# Control_and_Sample.net
KiCad netlist of a schematic drawn in Altium Designer
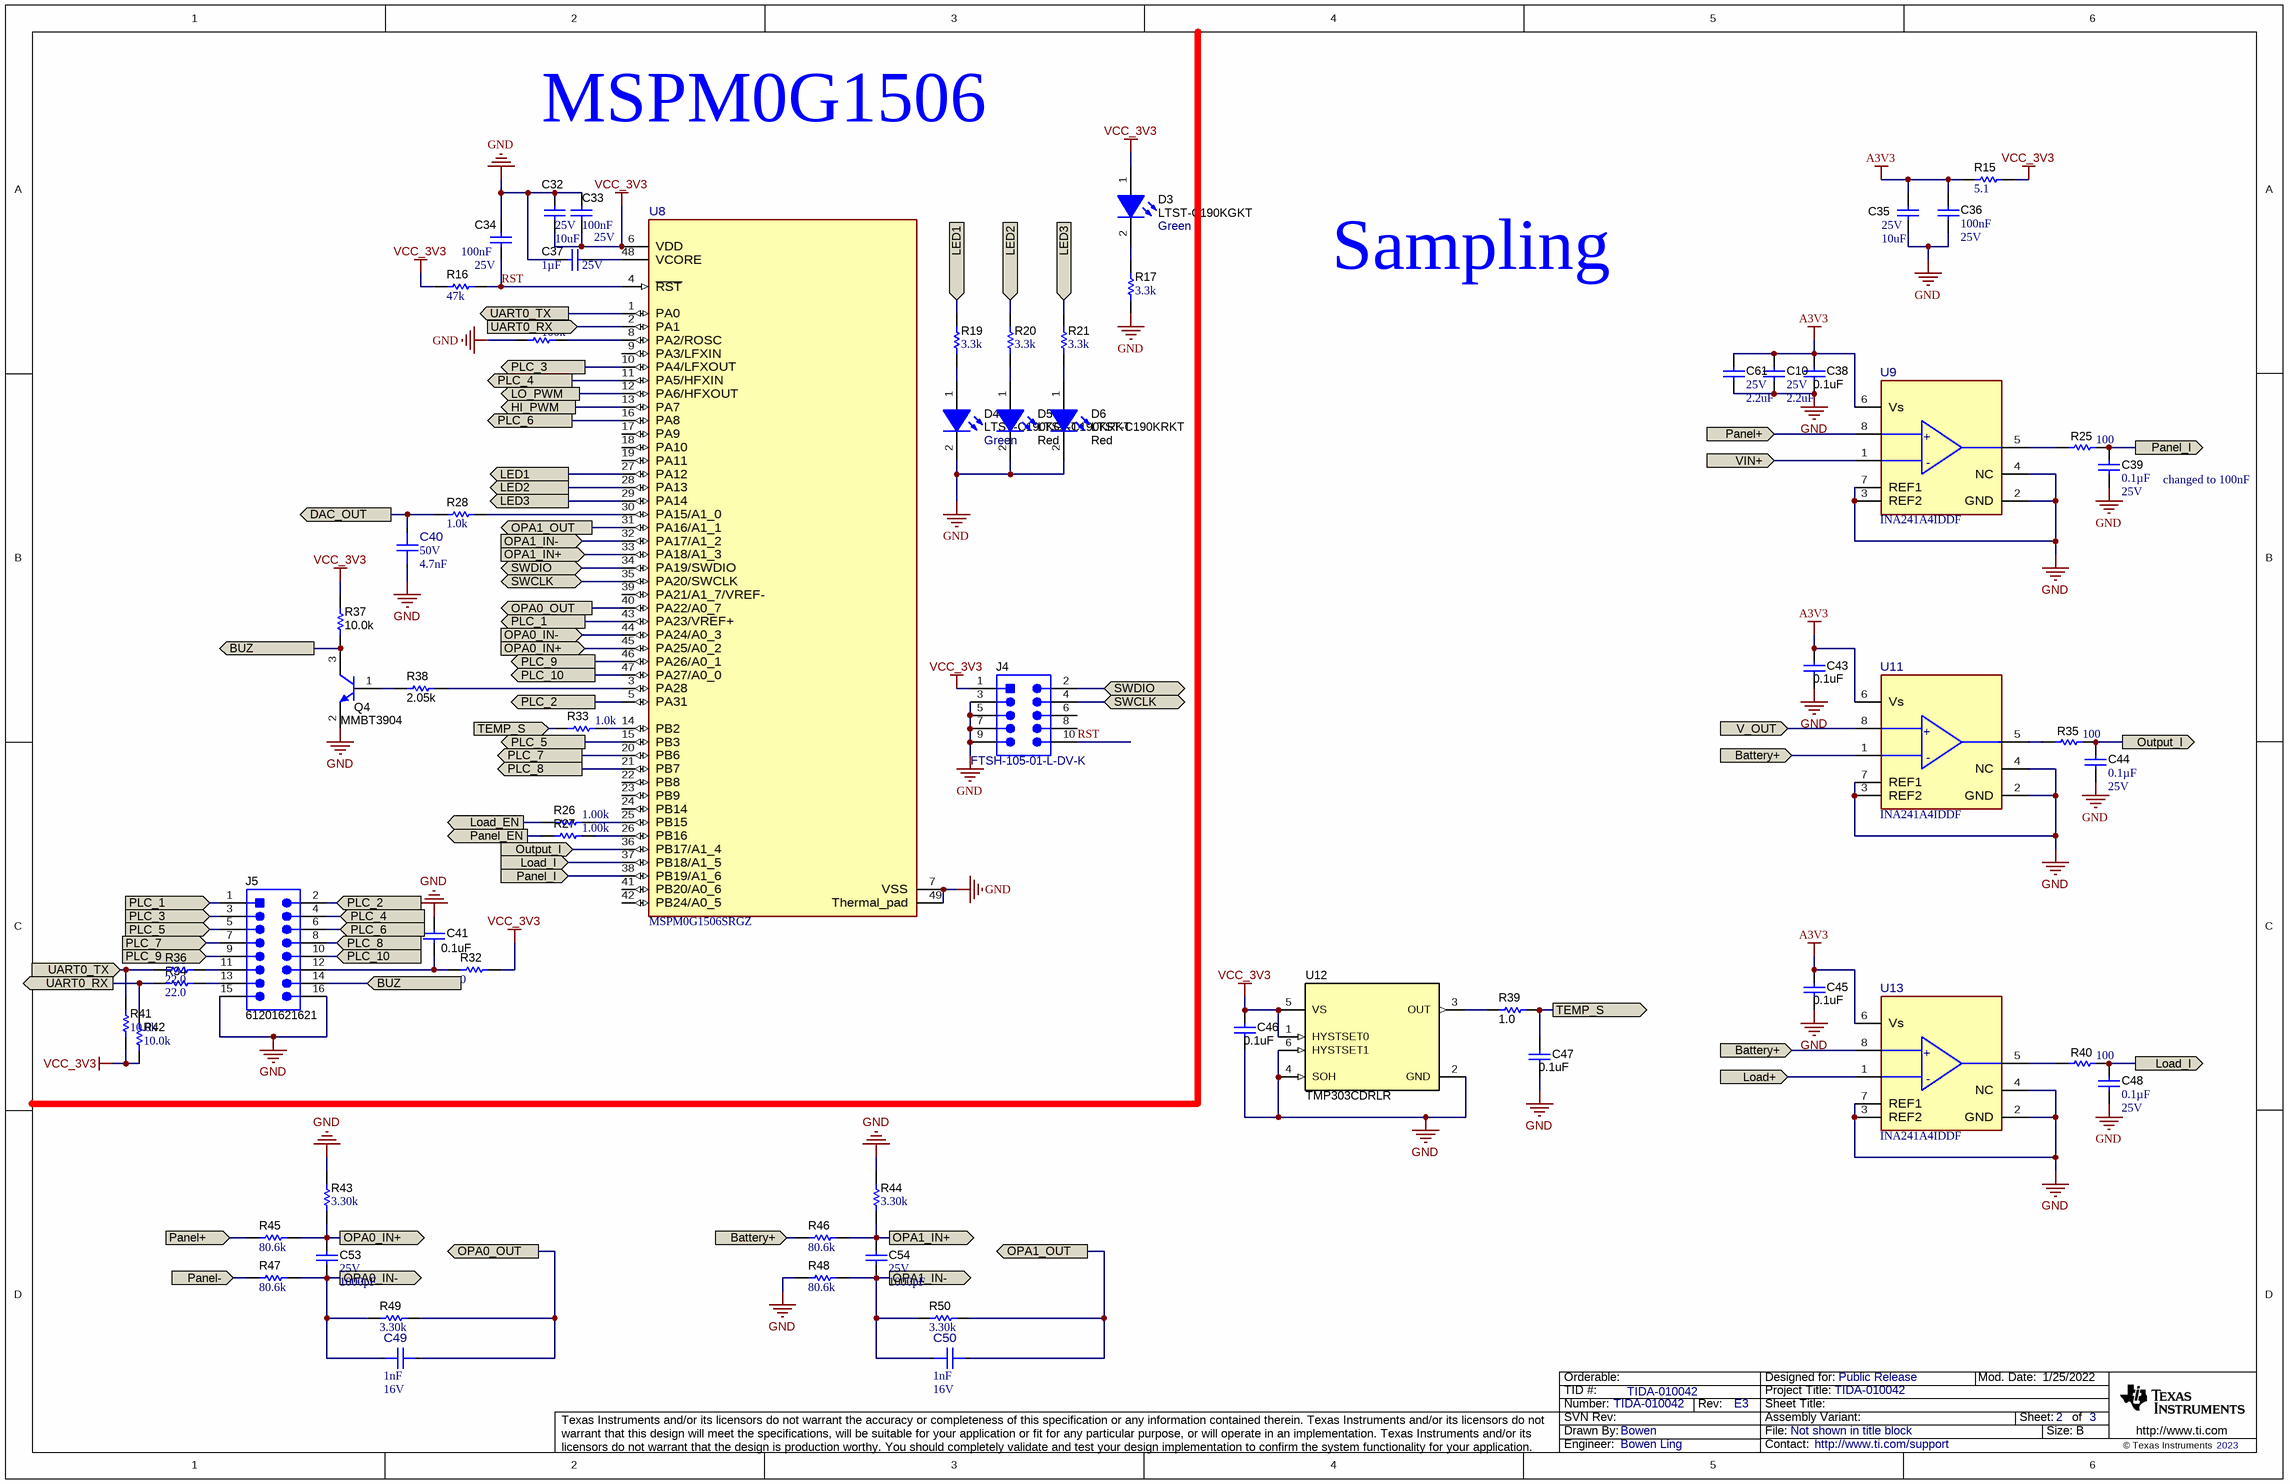
[diagram p0: Control and Sample.SchDoc]

(export (version "E")
  (design (tool "Eeschema 10.0.6"))
  (components
    (comp (ref "C10")
      (value "C1005X5R1E225K050BC")
      (footprint "0402")
      (description "CAP, CERM, 2.2 uF, 25 V, +/- 10%, X5R, 0402")
      (fields
        (field (name "MANUFACTURER") "TDK")
        (field (name "VDC_V") "25V")
        (field (name "VALUEDISPLAYED") "2.2uF")
        (field (name "PUBLISHER") "Texas Instruments")
      )
      (libsource (lib "Altium Vault - TI") (part "Capacitor"))
    )
    (comp (ref "C32")
      (value "GRM31CR71E106KA12L")
      (footprint "1206_180")
      (description "CAP, CERM, 10 uF, 25 V, +/- 10%, X7R, 1206")
      (fields
        (field (name "MANUFACTURER") "MuRata")
        (field (name "VDC_V") "25V")
        (field (name "VALUEDISPLAYED") "10uF")
        (field (name "PUBLISHER") "Texas Instruments")
      )
      (libsource (lib "Altium Vault - TI") (part "Capacitor"))
    )
    (comp (ref "C33")
      (value "GRM188R71E104KA01D")
      (footprint "0603")
      (description "CAP, CERM, 0.1 uF, 25 V, +/- 10%, X7R, 0603")
      (fields
        (field (name "MANUFACTURER") "MuRata")
        (field (name "CAP_F") "100nF")
        (field (name "VDC_V") "25V")
        (field (name "PUBLISHER") "Texas Instruments")
      )
      (libsource (lib "Altium Vault - TI") (part "Capacitor"))
    )
    (comp (ref "C34")
      (value "GRM188R71E104KA01D")
      (footprint "0603")
      (description "CAP, CERM, 0.1 uF, 25 V, +/- 10%, X7R, 0603")
      (fields
        (field (name "MANUFACTURER") "MuRata")
        (field (name "CAP_F") "100nF")
        (field (name "VDC_V") "25V")
        (field (name "PUBLISHER") "Texas Instruments")
      )
      (libsource (lib "Altium Vault - TI") (part "Capacitor"))
    )
    (comp (ref "C35")
      (value "GRM31CR71E106KA12L")
      (footprint "1206_180")
      (description "CAP, CERM, 10 uF, 25 V, +/- 10%, X7R, 1206")
      (fields
        (field (name "MANUFACTURER") "MuRata")
        (field (name "VDC_V") "25V")
        (field (name "VALUEDISPLAYED") "10uF")
        (field (name "PUBLISHER") "Texas Instruments")
      )
      (libsource (lib "Altium Vault - TI") (part "Capacitor"))
    )
    (comp (ref "C36")
      (value "GRM188R71E104KA01D")
      (footprint "0603")
      (description "CAP, CERM, 0.1 uF, 25 V, +/- 10%, X7R, 0603")
      (fields
        (field (name "MANUFACTURER") "MuRata")
        (field (name "CAP_F") "100nF")
        (field (name "VDC_V") "25V")
        (field (name "PUBLISHER") "Texas Instruments")
      )
      (libsource (lib "Altium Vault - TI") (part "Capacitor"))
    )
    (comp (ref "C37")
      (value "06033C105KAT2A")
      (footprint "0603")
      (description "CAP, CERM, 1 uF, 25 V, +/- 10%, X7R, 0603")
      (fields
        (field (name "MANUFACTURER") "AVX")
        (field (name "CAP_F") "1µF")
        (field (name "VDC_V") "25V")
        (field (name "PUBLISHER") "Texas Instruments")
      )
      (libsource (lib "Altium Vault - TI") (part "Capacitor"))
    )
    (comp (ref "C38")
      (value "GMK107BJ104KAHT")
      (footprint "0603")
      (description "CAP CER 0.1UF 25V X5R 0603")
      (fields
        (field (name "MANUFACTURER") "Taiyo Yuden")
        (field (name "PARTNUMBER") "TMK107BJ104KA-T")
        (field (name "VALUEDISPLAYED") "0.1uF")
        (field (name "PUBLISHER") "Texas Instruments")
      )
      (libsource (lib "Altium Vault - TI") (part "CMP-0007044-5"))
    )
    (comp (ref "C39")
      (value "GCM155L81E104KE02D")
      (footprint "0402")
      (description "CAP, CERM, 0.1 µF, 25 V,+/- 10%, X8L, AEC-Q200 Grade 0, 0402")
      (fields
        (field (name "MANUFACTURER") "MuRata")
        (field (name "VALUEDISPLAYED") "0.1µF")
        (field (name "VDC_V") "25V")
      )
      (libsource (lib "Altium Vault - TI") (part "Capacitor"))
    )
    (comp (ref "C40")
      (value "GRM188R71H472KA01J")
      (footprint "FP-GRM188R71H472KA01B_0603-MFG")
      (description "Multilayer Ceramic Capacitors MLCC - SMD/SMT 0603 4700pF 50volt X7R +/-10%")
      (fields
        (field (name "MOUSER PART NUMBER") "81-GRM18R71H472KA01B")
        (field (name "VDC_V") "50V")
        (field (name "CAP_F") "4.7nF")
        (field (name "PART NUMBER") "GRM188R71H472KA01B")
      )
      (libsource (lib "Altium Vault - TI") (part "SYM-GRM188R71H472KA01B"))
    )
    (comp (ref "C41")
      (value "GMK107BJ104KAHT")
      (footprint "0603")
      (description "CAP CER 0.1UF 25V X5R 0603")
      (fields
        (field (name "MANUFACTURER") "Taiyo Yuden")
        (field (name "PARTNUMBER") "TMK107BJ104KA-T")
        (field (name "VALUEDISPLAYED") "0.1uF")
        (field (name "PUBLISHER") "Texas Instruments")
      )
      (libsource (lib "Altium Vault - TI") (part "CMP-0007044-5"))
    )
    (comp (ref "C43")
      (value "GMK107BJ104KAHT")
      (footprint "0603")
      (description "CAP CER 0.1UF 25V X5R 0603")
      (fields
        (field (name "MANUFACTURER") "Taiyo Yuden")
        (field (name "PARTNUMBER") "TMK107BJ104KA-T")
        (field (name "VALUEDISPLAYED") "0.1uF")
        (field (name "PUBLISHER") "Texas Instruments")
      )
      (libsource (lib "Altium Vault - TI") (part "CMP-0007044-5"))
    )
    (comp (ref "C44")
      (value "GCM155L81E104KE02D")
      (footprint "0402")
      (description "CAP, CERM, 0.1 µF, 25 V,+/- 10%, X8L, AEC-Q200 Grade 0, 0402")
      (fields
        (field (name "MANUFACTURER") "MuRata")
        (field (name "VALUEDISPLAYED") "0.1µF")
        (field (name "VDC_V") "25V")
      )
      (libsource (lib "Altium Vault - TI") (part "Capacitor"))
    )
    (comp (ref "C45")
      (value "GMK107BJ104KAHT")
      (footprint "0603")
      (description "CAP CER 0.1UF 25V X5R 0603")
      (fields
        (field (name "MANUFACTURER") "Taiyo Yuden")
        (field (name "PARTNUMBER") "TMK107BJ104KA-T")
        (field (name "VALUEDISPLAYED") "0.1uF")
        (field (name "PUBLISHER") "Texas Instruments")
      )
      (libsource (lib "Altium Vault - TI") (part "CMP-0007044-5"))
    )
    (comp (ref "C46")
      (value "GMK107BJ104KAHT")
      (footprint "0603")
      (description "CAP CER 0.1UF 25V X5R 0603")
      (fields
        (field (name "MANUFACTURER") "Taiyo Yuden")
        (field (name "PARTNUMBER") "TMK107BJ104KA-T")
        (field (name "VALUEDISPLAYED") "0.1uF")
        (field (name "PUBLISHER") "Texas Instruments")
      )
      (libsource (lib "Altium Vault - TI") (part "CMP-0007044-5"))
    )
    (comp (ref "C47")
      (value "GMK107BJ104KAHT")
      (footprint "0603")
      (description "CAP CER 0.1UF 25V X5R 0603")
      (fields
        (field (name "MANUFACTURER") "Taiyo Yuden")
        (field (name "PARTNUMBER") "TMK107BJ104KA-T")
        (field (name "VALUEDISPLAYED") "0.1uF")
        (field (name "PUBLISHER") "Texas Instruments")
      )
      (libsource (lib "Altium Vault - TI") (part "CMP-0007044-5"))
    )
    (comp (ref "C48")
      (value "GCM155L81E104KE02D")
      (footprint "0402")
      (description "CAP, CERM, 0.1 µF, 25 V,+/- 10%, X8L, AEC-Q200 Grade 0, 0402")
      (fields
        (field (name "MANUFACTURER") "MuRata")
        (field (name "VALUEDISPLAYED") "0.1µF")
        (field (name "VDC_V") "25V")
      )
      (libsource (lib "Altium Vault - TI") (part "Capacitor"))
    )
    (comp (ref "C49")
      (value "CC0603KRX7R7BB102")
      (footprint "FP-CC0603KRX7R7BB102_0603-MFG")
      (description "1000 pF ±10% 16V Ceramic Capacitor X7R 0603 (1608 Metric)")
      (fields
        (field (name "MOUSER PART NUMBER") "603-CC603KRX7R7BB102")
        (field (name "MANUFACTURER") "YAGEO")
        (field (name "CAP_F") "1nF")
        (field (name "VDC_V") "16V")
      )
      (libsource (lib "Altium Vault - TI") (part "SYM-CC0603KRX7R7BB102"))
    )
    (comp (ref "C50")
      (value "CC0603KRX7R7BB102")
      (footprint "FP-CC0603KRX7R7BB102_0603-MFG")
      (description "1000 pF ±10% 16V Ceramic Capacitor X7R 0603 (1608 Metric)")
      (fields
        (field (name "MOUSER PART NUMBER") "603-CC603KRX7R7BB102")
        (field (name "MANUFACTURER") "YAGEO")
        (field (name "CAP_F") "1nF")
        (field (name "VDC_V") "16V")
      )
      (libsource (lib "Altium Vault - TI") (part "SYM-CC0603KRX7R7BB102"))
    )
    (comp (ref "C53")
      (value "C0402C102J3RACTU")
      (footprint "0402")
      (description "CAP, CERM, 1000 pF, 25 V, +/- 5%, X7R, 0402")
      (fields
        (field (name "MANUFACTURER") "Kemet")
        (field (name "VDC_V") "25V")
        (field (name "VALUEDISPLAYED") "1000pF")
        (field (name "PUBLISHER") "Texas Instruments")
      )
      (libsource (lib "Altium Vault - TI") (part "Capacitor"))
    )
    (comp (ref "C54")
      (value "C0402C102J3RACTU")
      (footprint "0402")
      (description "CAP, CERM, 1000 pF, 25 V, +/- 5%, X7R, 0402")
      (fields
        (field (name "MANUFACTURER") "Kemet")
        (field (name "VDC_V") "25V")
        (field (name "VALUEDISPLAYED") "1000pF")
        (field (name "PUBLISHER") "Texas Instruments")
      )
      (libsource (lib "Altium Vault - TI") (part "Capacitor"))
    )
    (comp (ref "C61")
      (value "C1005X5R1E225K050BC")
      (footprint "0402")
      (description "CAP, CERM, 2.2 uF, 25 V, +/- 10%, X5R, 0402")
      (fields
        (field (name "MANUFACTURER") "TDK")
        (field (name "VDC_V") "25V")
        (field (name "VALUEDISPLAYED") "2.2uF")
        (field (name "PUBLISHER") "Texas Instruments")
      )
      (libsource (lib "Altium Vault - TI") (part "Capacitor"))
    )
    (comp (ref "D3")
      (value "LTST-C190KGKT")
      (footprint "LED_LTST-C190_G")
      (description "LED, Green, SMD")
      (fields (field (name "ALTIUM_VALUE") "Green") (field (name "MANUFACTURER") "Lite-On"))
      (libsource (lib "Altium Vault - TI") (part "LED"))
    )
    (comp (ref "D4")
      (value "LTST-C190KGKT")
      (footprint "LED_LTST-C190_G")
      (description "LED, Green, SMD")
      (fields (field (name "ALTIUM_VALUE") "Green") (field (name "MANUFACTURER") "Lite-On"))
      (libsource (lib "Altium Vault - TI") (part "LED"))
    )
    (comp (ref "D5")
      (value "LTST-C190KRKT")
      (footprint "LED_LTST-C190_Red")
      (description "LED, Red, SMD")
      (fields (field (name "ALTIUM_VALUE") "Red") (field (name "MANUFACTURER") "Lite-On"))
      (libsource (lib "Altium Vault - TI") (part "LED"))
    )
    (comp (ref "D6")
      (value "LTST-C190KRKT")
      (footprint "LED_LTST-C190_Red")
      (description "LED, Red, SMD")
      (fields (field (name "ALTIUM_VALUE") "Red") (field (name "MANUFACTURER") "Lite-On"))
      (libsource (lib "Altium Vault - TI") (part "LED"))
    )
    (comp (ref "J4")
      (value "FTSH-105-01-L-DV-K")
      (footprint "Samtec_FTSH-105-01-x-DV-K")
      (description "Header(Shrouded), 1.27mm, 5x2, Gold, SMT")
      (fields (field (name "MANUFACTURER") "Samtec") (field (name "PUBLISHER") "Texas Instruments"))
      (libsource (lib "Altium Vault - TI") (part "Header_5x2"))
    )
    (comp (ref "J5")
      (value "61201621621")
      (footprint "Wurth_61201621621")
      (description "Header(Shrouded), 2.54mm, 8x2, Gold, TH")
      (fields (field (name "MANUFACTURER") "Wurth Elektronik") (field (name "PUBLISHER") "Texas Instruments"))
      (libsource (lib "Altium Vault - TI") (part "Header_8x2"))
    )
    (comp (ref "Q4")
      (value "MMBT3904")
      (footprint "SOT-23")
      (description "TRANS NPN 40V 0.2A SOT23")
      (fields
        (field (name "PARTNUMBER") "MMBT3904-TP")
        (field (name "MANUFACTURER") "Micro Commercial Co")
        (field (name "PUBLISHER") "Texas Instruments")
      )
      (libsource (lib "Altium Vault - TI") (part "CMP-0000386-2"))
    )
    (comp (ref "R15")
      (value "CRCW06035R10JNEA")
      (footprint "0603")
      (description "RES, 5.1, 5%, 0.1 W, 0603")
      (fields
        (field (name "MANUFACTURER") "Vishay-Dale")
        (field (name "VALUEDISPLAYED") "5.1")
        (field (name "PUBLISHER") "Texas Instruments")
      )
      (libsource (lib "Altium Vault - TI") (part "Resistor"))
    )
    (comp (ref "R16")
      (value "RC0603JR-0747KL")
      (footprint "0603")
      (description "RES, 47 k, 5%, 0.1 W, 0603")
      (fields (field (name "MANUFACTURER") "Yageo") (field (name "VALUEDISPLAYED") "47k"))
      (libsource (lib "Altium Vault - TI") (part "Resistor"))
    )
    (comp (ref "R17")
      (value "CRCW06033K30JNEA")
      (footprint "0603")
      (description "RES, 3.3 k, 5%, 0.1 W, AEC-Q200 Grade 0, 0603")
      (fields (field (name "MANUFACTURER") "Vishay-Dale") (field (name "VALUEDISPLAYED") "3.3k"))
      (libsource (lib "Altium Vault - TI") (part "Resistor"))
    )
    (comp (ref "R18")
      (value "RT0603BRD07100KL")
      (footprint "0603")
      (description "RES, 100 k, 0.1%, 0.1 W, 0603")
      (fields
        (field (name "MANUFACTURER") "Yageo America")
        (field (name "VALUEDISPLAYED") "100k")
        (field (name "PUBLISHER") "Texas Instruments")
      )
      (libsource (lib "Altium Vault - TI") (part "Resistor"))
    )
    (comp (ref "R19")
      (value "CRCW06033K30JNEA")
      (footprint "0603")
      (description "RES, 3.3 k, 5%, 0.1 W, AEC-Q200 Grade 0, 0603")
      (fields (field (name "MANUFACTURER") "Vishay-Dale") (field (name "VALUEDISPLAYED") "3.3k"))
      (libsource (lib "Altium Vault - TI") (part "Resistor"))
    )
    (comp (ref "R20")
      (value "CRCW06033K30JNEA")
      (footprint "0603")
      (description "RES, 3.3 k, 5%, 0.1 W, AEC-Q200 Grade 0, 0603")
      (fields (field (name "MANUFACTURER") "Vishay-Dale") (field (name "VALUEDISPLAYED") "3.3k"))
      (libsource (lib "Altium Vault - TI") (part "Resistor"))
    )
    (comp (ref "R21")
      (value "CRCW06033K30JNEA")
      (footprint "0603")
      (description "RES, 3.3 k, 5%, 0.1 W, AEC-Q200 Grade 0, 0603")
      (fields (field (name "MANUFACTURER") "Vishay-Dale") (field (name "VALUEDISPLAYED") "3.3k"))
      (libsource (lib "Altium Vault - TI") (part "Resistor"))
    )
    (comp (ref "R25")
      (value "RC0603FR-07100RL")
      (footprint "0603")
      (description "RES, 100, 1%, 0.1 W, 0603")
      (fields (field (name "MANUFACTURER") "Yageo") (field (name "VALUEDISPLAYED") "100"))
      (libsource (lib "Altium Vault - TI") (part "Resistor"))
    )
    (comp (ref "R26")
      (value "RC0603FR-071KL")
      (footprint "0603")
      (description "RES, 1.00 k, 1%, 0.1 W, 0603")
      (fields (field (name "MANUFACTURER") "Yageo") (field (name "VALUEDISPLAYED") "1.00k"))
      (libsource (lib "Altium Vault - TI") (part "Resistor"))
    )
    (comp (ref "R27")
      (value "RC0603FR-071KL")
      (footprint "0603")
      (description "RES, 1.00 k, 1%, 0.1 W, 0603")
      (fields (field (name "MANUFACTURER") "Yageo") (field (name "VALUEDISPLAYED") "1.00k"))
      (libsource (lib "Altium Vault - TI") (part "Resistor"))
    )
    (comp (ref "R28")
      (value "RC0603JR-071KL")
      (footprint "0603")
      (description "RES, 1.0 k, 5%, 0.1 W, 0603")
      (fields (field (name "MANUFACTURER") "Yageo") (field (name "VALUEDISPLAYED") "1.0k"))
      (libsource (lib "Altium Vault - TI") (part "Resistor"))
    )
    (comp (ref "R32")
      (value "RC0603JR-070RL")
      (footprint "0603")
      (description "RES, 0, 5%, 0.1 W, 0603")
      (fields (field (name "MANUFACTURER") "Yageo") (field (name "VALUEDISPLAYED") "0"))
      (libsource (lib "Altium Vault - TI") (part "Resistor"))
    )
    (comp (ref "R33")
      (value "RC0603JR-071KL")
      (footprint "0603")
      (description "RES, 1.0 k, 5%, 0.1 W, 0603")
      (fields (field (name "MANUFACTURER") "Yageo") (field (name "VALUEDISPLAYED") "1.0k"))
      (libsource (lib "Altium Vault - TI") (part "Resistor"))
    )
    (comp (ref "R34")
      (value "RC0603FR-0722RL")
      (footprint "0603")
      (description "RES, 22.0, 1%, 0.1 W, 0603")
      (fields (field (name "MANUFACTURER") "Yageo") (field (name "VALUEDISPLAYED") "22.0"))
      (libsource (lib "Altium Vault - TI") (part "Resistor"))
    )
    (comp (ref "R35")
      (value "RC0603FR-07100RL")
      (footprint "0603")
      (description "RES, 100, 1%, 0.1 W, 0603")
      (fields (field (name "MANUFACTURER") "Yageo") (field (name "VALUEDISPLAYED") "100"))
      (libsource (lib "Altium Vault - TI") (part "Resistor"))
    )
    (comp (ref "R36")
      (value "RC0603FR-0722RL")
      (footprint "0603")
      (description "RES, 22.0, 1%, 0.1 W, 0603")
      (fields (field (name "MANUFACTURER") "Yageo") (field (name "VALUEDISPLAYED") "22.0"))
      (libsource (lib "Altium Vault - TI") (part "Resistor"))
    )
    (comp (ref "R37")
      (value "ERJ-3EKF1002V")
      (footprint "0603")
      (description "RES, 10.0 k, 1%, 0.1 W, 0603")
      (fields
        (field (name "MANUFACTURER") "Panasonic")
        (field (name "VALUEDISPLAYED") "10.0k")
        (field (name "PUBLISHER") "Texas Instruments")
      )
      (libsource (lib "Altium Vault - TI") (part "Resistor"))
    )
    (comp (ref "R38")
      (value "RC0603FR-072K05L")
      (footprint "0603")
      (description "RES, 2.05 k, 1%, 0.1 W, 0603")
      (fields (field (name "MANUFACTURER") "Yageo") (field (name "VALUEDISPLAYED") "2.05k"))
      (libsource (lib "Altium Vault - TI") (part "Resistor"))
    )
    (comp (ref "R39")
      (value "CRCW06031R00JNEA")
      (footprint "0603")
      (description "RES, 1.0, 5%, 0.1 W, AEC-Q200 Grade 0, 0603")
      (fields (field (name "MANUFACTURER") "Vishay-Dale") (field (name "VALUEDISPLAYED") "1.0"))
      (libsource (lib "Altium Vault - TI") (part "Resistor"))
    )
    (comp (ref "R40")
      (value "RC0603FR-07100RL")
      (footprint "0603")
      (description "RES, 100, 1%, 0.1 W, 0603")
      (fields (field (name "MANUFACTURER") "Yageo") (field (name "VALUEDISPLAYED") "100"))
      (libsource (lib "Altium Vault - TI") (part "Resistor"))
    )
    (comp (ref "R41")
      (value "RMCF0603FT10K0")
      (footprint "0603")
      (description "RES, 10.0 k, 1%, 0.1 W, AEC-Q200 Grade 0, 0603")
      (fields
        (field (name "MANUFACTURER") "Stackpole Electronics Inc")
        (field (name "VALUEDISPLAYED") "10.0k")
        (field (name "PUBLISHER") "Texas Instruments")
      )
      (libsource (lib "Altium Vault - TI") (part "Resistor"))
    )
    (comp (ref "R42")
      (value "RMCF0603FT10K0")
      (footprint "0603")
      (description "RES, 10.0 k, 1%, 0.1 W, AEC-Q200 Grade 0, 0603")
      (fields
        (field (name "MANUFACTURER") "Stackpole Electronics Inc")
        (field (name "VALUEDISPLAYED") "10.0k")
        (field (name "PUBLISHER") "Texas Instruments")
      )
      (libsource (lib "Altium Vault - TI") (part "Resistor"))
    )
    (comp (ref "R43")
      (value "CRCW06033K30FKEA")
      (footprint "0603")
      (description "RES, 3.30 k, 1%, 0.1 W, AEC-Q200 Grade 0, 0603")
      (fields (field (name "MANUFACTURER") "Vishay-Dale") (field (name "VALUEDISPLAYED") "3.30k"))
      (libsource (lib "Altium Vault - TI") (part "Resistor"))
    )
    (comp (ref "R44")
      (value "CRCW06033K30FKEA")
      (footprint "0603")
      (description "RES, 3.30 k, 1%, 0.1 W, AEC-Q200 Grade 0, 0603")
      (fields (field (name "MANUFACTURER") "Vishay-Dale") (field (name "VALUEDISPLAYED") "3.30k"))
      (libsource (lib "Altium Vault - TI") (part "Resistor"))
    )
    (comp (ref "R45")
      (value "RC0603FR-0780K6L")
      (footprint "0603")
      (description "RES, 80.6 k, 1%, 0.1 W, 0603")
      (fields (field (name "MANUFACTURER") "Yageo") (field (name "VALUEDISPLAYED") "80.6k"))
      (libsource (lib "Altium Vault - TI") (part "Resistor"))
    )
    (comp (ref "R46")
      (value "RC0603FR-0780K6L")
      (footprint "0603")
      (description "RES, 80.6 k, 1%, 0.1 W, 0603")
      (fields (field (name "MANUFACTURER") "Yageo") (field (name "VALUEDISPLAYED") "80.6k"))
      (libsource (lib "Altium Vault - TI") (part "Resistor"))
    )
    (comp (ref "R47")
      (value "RC0603FR-0780K6L")
      (footprint "0603")
      (description "RES, 80.6 k, 1%, 0.1 W, 0603")
      (fields (field (name "MANUFACTURER") "Yageo") (field (name "VALUEDISPLAYED") "80.6k"))
      (libsource (lib "Altium Vault - TI") (part "Resistor"))
    )
    (comp (ref "R48")
      (value "RC0603FR-0780K6L")
      (footprint "0603")
      (description "RES, 80.6 k, 1%, 0.1 W, 0603")
      (fields (field (name "MANUFACTURER") "Yageo") (field (name "VALUEDISPLAYED") "80.6k"))
      (libsource (lib "Altium Vault - TI") (part "Resistor"))
    )
    (comp (ref "R49")
      (value "CRCW06033K30FKEA")
      (footprint "0603")
      (description "RES, 3.30 k, 1%, 0.1 W, AEC-Q200 Grade 0, 0603")
      (fields (field (name "MANUFACTURER") "Vishay-Dale") (field (name "VALUEDISPLAYED") "3.30k"))
      (libsource (lib "Altium Vault - TI") (part "Resistor"))
    )
    (comp (ref "R50")
      (value "CRCW06033K30FKEA")
      (footprint "0603")
      (description "RES, 3.30 k, 1%, 0.1 W, AEC-Q200 Grade 0, 0603")
      (fields (field (name "MANUFACTURER") "Vishay-Dale") (field (name "VALUEDISPLAYED") "3.30k"))
      (libsource (lib "Altium Vault - TI") (part "Resistor"))
    )
    (comp (ref "U8")
      (value "MSPM0G1506SRGZ")
      (footprint "RGZ0048B-MFG")
      (description "Mixed-Signal Microcontrollers")
      (fields
        (field (name "PART NUMBER") "MSPM0G1507SRGZ")
        (field (name "MANUFACTURER") "Texas Instruments")
        (field (name "PARTNUMBER") "MSPM0G1506SRGZ")
      )
      (libsource (lib "Altium Vault - TI") (part "SYM-MSPM0G1507SRGZ"))
    )
    (comp (ref "U9")
      (value "INA241A4IDDF")
      (footprint "DDF0008A-MFG")
      (description "-4-V to 110-V, Bidirectional, Ultra-Precise Current Sense Amplifier With Enhanced PWM Rejection")
      (fields (field (name "PARTNUMBER") "INA241A4IDDF") (field (name "MANUFACTURER") "Texas Instruments"))
      (libsource (lib "Altium Vault - TI") (part "SYM-INA241A4DDF"))
    )
    (comp (ref "U11")
      (value "INA241A4IDDF")
      (footprint "DDF0008A-MFG")
      (description "-4-V to 110-V, Bidirectional, Ultra-Precise Current Sense Amplifier With Enhanced PWM Rejection")
      (fields (field (name "PARTNUMBER") "INA241A4IDDF") (field (name "MANUFACTURER") "Texas Instruments"))
      (libsource (lib "Altium Vault - TI") (part "SYM-INA241A4DDF"))
    )
    (comp (ref "U12")
      (value "TMP303CDRLR")
      (footprint "DRL0006A")
      (description "Factory Programmed Temperature Window Comparator, DRL0006A (SOT-OTHER-6)")
      (fields
        (field (name "ALTERNATE PARTNUMBER") "TMP303CDRLT")
        (field (name "MANUFACTURER") "Texas Instruments")
        (field (name "PARTNUMBER") "TMP303CDRLR")
        (field (name "PUBLISHER") "Texas Instruments")
      )
      (libsource (lib "Altium Vault - TI") (part "CMP-0074735-2"))
    )
    (comp (ref "U13")
      (value "INA241A4IDDF")
      (footprint "DDF0008A-MFG")
      (description "-4-V to 110-V, Bidirectional, Ultra-Precise Current Sense Amplifier With Enhanced PWM Rejection")
      (fields (field (name "PARTNUMBER") "INA241A4IDDF") (field (name "MANUFACTURER") "Texas Instruments"))
      (libsource (lib "Altium Vault - TI") (part "SYM-INA241A4DDF"))
    )
  )
  (nets
    (net (code "1") (name "/BUZ") (class "Default")
      (node (ref "J5") (pin "14") (pinfunction "14_14") (pintype "passive"))
      (node (ref "Q4") (pin "3") (pinfunction "C_3") (pintype "passive"))
      (node (ref "R37") (pin "2") (pinfunction "2_2") (pintype "passive"))
    )
    (net (code "2") (name "/Battery+") (class "Default")
      (node (ref "R46") (pin "1") (pinfunction "1_1") (pintype "passive"))
      (node (ref "U11") (pin "1") (pinfunction "IN-_1") (pintype "tri_state"))
      (node (ref "U13") (pin "8") (pinfunction "IN+_8") (pintype "tri_state"))
    )
    (net (code "3") (name "/DAC_OUT") (class "Default")
      (node (ref "C40") (pin "2") (pinfunction "2_2") (pintype "passive"))
      (node (ref "R28") (pin "1") (pinfunction "1_1") (pintype "passive"))
    )
    (net (code "4") (name "/HI_PWM") (class "Default")
      (node (ref "U8") (pin "13") (pinfunction "PA7_13") (pintype "bidirectional"))
    )
    (net (code "5") (name "/LED1") (class "Default")
      (node (ref "R19") (pin "1") (pinfunction "1_1") (pintype "passive"))
      (node (ref "U8") (pin "27") (pinfunction "PA12_27") (pintype "bidirectional"))
    )
    (net (code "6") (name "/LED2") (class "Default")
      (node (ref "R20") (pin "1") (pinfunction "1_1") (pintype "passive"))
      (node (ref "U8") (pin "28") (pinfunction "PA13_28") (pintype "bidirectional"))
    )
    (net (code "7") (name "/LED3") (class "Default")
      (node (ref "R21") (pin "1") (pinfunction "1_1") (pintype "passive"))
      (node (ref "U8") (pin "29") (pinfunction "PA14_29") (pintype "bidirectional"))
    )
    (net (code "8") (name "/LO_PWM") (class "Default")
      (node (ref "U8") (pin "12") (pinfunction "PA6/HFXOUT_12") (pintype "bidirectional"))
    )
    (net (code "9") (name "/Load+") (class "Default")
      (node (ref "U13") (pin "1") (pinfunction "IN-_1") (pintype "tri_state"))
    )
    (net (code "10") (name "/Load_EN") (class "Default")
      (node (ref "R26") (pin "1") (pinfunction "1_1") (pintype "passive"))
    )
    (net (code "11") (name "/Load_I") (class "Default")
      (node (ref "C48") (pin "1") (pinfunction "1_1") (pintype "passive"))
      (node (ref "R40") (pin "2") (pinfunction "2_2") (pintype "passive"))
      (node (ref "U8") (pin "37") (pinfunction "PB18/A1_5_37") (pintype "bidirectional"))
    )
    (net (code "12") (name "/OPA0_IN+") (class "Default")
      (node (ref "C53") (pin "1") (pinfunction "1_1") (pintype "passive"))
      (node (ref "R43") (pin "1") (pinfunction "1_1") (pintype "passive"))
      (node (ref "R45") (pin "2") (pinfunction "2_2") (pintype "passive"))
      (node (ref "U8") (pin "45") (pinfunction "PA25/A0_2_45") (pintype "bidirectional"))
    )
    (net (code "13") (name "/OPA0_IN-") (class "Default")
      (node (ref "C49") (pin "1") (pinfunction "1_1") (pintype "passive"))
      (node (ref "C53") (pin "2") (pinfunction "2_2") (pintype "passive"))
      (node (ref "R47") (pin "2") (pinfunction "2_2") (pintype "passive"))
      (node (ref "R49") (pin "1") (pinfunction "1_1") (pintype "passive"))
      (node (ref "U8") (pin "44") (pinfunction "PA24/A0_3_44") (pintype "bidirectional"))
    )
    (net (code "14") (name "/OPA0_OUT") (class "Default")
      (node (ref "C49") (pin "2") (pinfunction "2_2") (pintype "passive"))
      (node (ref "R49") (pin "2") (pinfunction "2_2") (pintype "passive"))
      (node (ref "U8") (pin "40") (pinfunction "PA22/A0_7_40") (pintype "bidirectional"))
    )
    (net (code "15") (name "/OPA1_IN+") (class "Default")
      (node (ref "C54") (pin "1") (pinfunction "1_1") (pintype "passive"))
      (node (ref "R44") (pin "1") (pinfunction "1_1") (pintype "passive"))
      (node (ref "R46") (pin "2") (pinfunction "2_2") (pintype "passive"))
      (node (ref "U8") (pin "33") (pinfunction "PA18/A1_3_33") (pintype "bidirectional"))
    )
    (net (code "16") (name "/OPA1_IN-") (class "Default")
      (node (ref "C50") (pin "1") (pinfunction "1_1") (pintype "passive"))
      (node (ref "C54") (pin "2") (pinfunction "2_2") (pintype "passive"))
      (node (ref "R48") (pin "2") (pinfunction "2_2") (pintype "passive"))
      (node (ref "R50") (pin "1") (pinfunction "1_1") (pintype "passive"))
      (node (ref "U8") (pin "32") (pinfunction "PA17/A1_2_32") (pintype "bidirectional"))
    )
    (net (code "17") (name "/OPA1_OUT") (class "Default")
      (node (ref "C50") (pin "2") (pinfunction "2_2") (pintype "passive"))
      (node (ref "R50") (pin "2") (pinfunction "2_2") (pintype "passive"))
      (node (ref "U8") (pin "31") (pinfunction "PA16/A1_1_31") (pintype "bidirectional"))
    )
    (net (code "18") (name "/Output_I") (class "Default")
      (node (ref "C44") (pin "1") (pinfunction "1_1") (pintype "passive"))
      (node (ref "R35") (pin "2") (pinfunction "2_2") (pintype "passive"))
      (node (ref "U8") (pin "36") (pinfunction "PB17/A1_4_36") (pintype "bidirectional"))
    )
    (net (code "19") (name "/PLC_1") (class "Default")
      (node (ref "J5") (pin "1") (pinfunction "1_1") (pintype "passive"))
      (node (ref "U8") (pin "43") (pinfunction "PA23/VREF+_43") (pintype "bidirectional"))
    )
    (net (code "20") (name "/PLC_2") (class "Default")
      (node (ref "J5") (pin "2") (pinfunction "2_2") (pintype "passive"))
      (node (ref "U8") (pin "5") (pinfunction "PA31_5") (pintype "bidirectional"))
    )
    (net (code "21") (name "/PLC_3") (class "Default")
      (node (ref "J5") (pin "3") (pinfunction "3_3") (pintype "passive"))
      (node (ref "U8") (pin "10") (pinfunction "PA4/LFXOUT_10") (pintype "bidirectional"))
    )
    (net (code "22") (name "/PLC_4") (class "Default")
      (node (ref "J5") (pin "4") (pinfunction "4_4") (pintype "passive"))
      (node (ref "U8") (pin "11") (pinfunction "PA5/HFXIN_11") (pintype "bidirectional"))
    )
    (net (code "23") (name "/PLC_5") (class "Default")
      (node (ref "J5") (pin "5") (pinfunction "5_5") (pintype "passive"))
      (node (ref "U8") (pin "15") (pinfunction "PB3_15") (pintype "bidirectional"))
    )
    (net (code "24") (name "/PLC_6") (class "Default")
      (node (ref "J5") (pin "6") (pinfunction "6_6") (pintype "passive"))
      (node (ref "U8") (pin "16") (pinfunction "PA8_16") (pintype "bidirectional"))
    )
    (net (code "25") (name "/PLC_7") (class "Default")
      (node (ref "J5") (pin "7") (pinfunction "7_7") (pintype "passive"))
      (node (ref "U8") (pin "20") (pinfunction "PB6_20") (pintype "bidirectional"))
    )
    (net (code "26") (name "/PLC_8") (class "Default")
      (node (ref "J5") (pin "8") (pinfunction "8_8") (pintype "passive"))
      (node (ref "U8") (pin "21") (pinfunction "PB7_21") (pintype "bidirectional"))
    )
    (net (code "27") (name "/PLC_9") (class "Default")
      (node (ref "J5") (pin "9") (pinfunction "9_9") (pintype "passive"))
      (node (ref "U8") (pin "46") (pinfunction "PA26/A0_1_46") (pintype "bidirectional"))
    )
    (net (code "28") (name "/PLC_10") (class "Default")
      (node (ref "J5") (pin "10") (pinfunction "10_10") (pintype "passive"))
      (node (ref "U8") (pin "47") (pinfunction "PA27/A0_0_47") (pintype "bidirectional"))
    )
    (net (code "29") (name "/Panel+") (class "Default")
      (node (ref "R45") (pin "1") (pinfunction "1_1") (pintype "passive"))
      (node (ref "U9") (pin "8") (pinfunction "IN+_8") (pintype "tri_state"))
    )
    (net (code "30") (name "/Panel-") (class "Default")
      (node (ref "R47") (pin "1") (pinfunction "1_1") (pintype "passive"))
    )
    (net (code "31") (name "/Panel_EN") (class "Default")
      (node (ref "R27") (pin "1") (pinfunction "1_1") (pintype "passive"))
    )
    (net (code "32") (name "/Panel_I") (class "Default")
      (node (ref "C39") (pin "1") (pinfunction "1_1") (pintype "passive"))
      (node (ref "R25") (pin "2") (pinfunction "2_2") (pintype "passive"))
      (node (ref "U8") (pin "38") (pinfunction "PB19/A1_6_38") (pintype "bidirectional"))
    )
    (net (code "33") (name "/RST") (class "Default")
      (node (ref "C34") (pin "2") (pinfunction "2_2") (pintype "passive"))
      (node (ref "J4") (pin "10") (pinfunction "10_10") (pintype "passive"))
      (node (ref "R16") (pin "2") (pinfunction "2_2") (pintype "passive"))
      (node (ref "U8") (pin "4") (pinfunction "~{RST}_4") (pintype "input"))
    )
    (net (code "34") (name "/SWCLK") (class "Default")
      (node (ref "J4") (pin "4") (pinfunction "4_4") (pintype "passive"))
      (node (ref "U8") (pin "35") (pinfunction "PA20/SWCLK_35") (pintype "bidirectional"))
    )
    (net (code "35") (name "/SWDIO") (class "Default")
      (node (ref "J4") (pin "2") (pinfunction "2_2") (pintype "passive"))
      (node (ref "U8") (pin "34") (pinfunction "PA19/SWDIO_34") (pintype "bidirectional"))
    )
    (net (code "36") (name "/TEMP_S") (class "Default")
      (node (ref "C47") (pin "1") (pinfunction "1_1") (pintype "passive"))
      (node (ref "R33") (pin "1") (pinfunction "1_1") (pintype "passive"))
      (node (ref "R39") (pin "2") (pinfunction "2_2") (pintype "passive"))
    )
    (net (code "37") (name "/UART0_RX") (class "Default")
      (node (ref "R34") (pin "1") (pinfunction "1_1") (pintype "passive"))
      (node (ref "R42") (pin "2") (pinfunction "2_2") (pintype "passive"))
      (node (ref "U8") (pin "2") (pinfunction "PA1_2") (pintype "bidirectional"))
    )
    (net (code "38") (name "/UART0_TX") (class "Default")
      (node (ref "R36") (pin "1") (pinfunction "1_1") (pintype "passive"))
      (node (ref "R41") (pin "2") (pinfunction "2_2") (pintype "passive"))
      (node (ref "U8") (pin "1") (pinfunction "PA0_1") (pintype "bidirectional"))
    )
    (net (code "39") (name "/VIN+") (class "Default")
      (node (ref "U9") (pin "1") (pinfunction "IN-_1") (pintype "tri_state"))
    )
    (net (code "40") (name "/V_OUT") (class "Default")
      (node (ref "U11") (pin "8") (pinfunction "IN+_8") (pintype "tri_state"))
    )
    (net (code "41") (name "A3V3") (class "Default")
      (node (ref "C10") (pin "1") (pinfunction "1_1") (pintype "passive"))
      (node (ref "C35") (pin "1") (pinfunction "1_1") (pintype "passive"))
      (node (ref "C36") (pin "1") (pinfunction "1_1") (pintype "passive"))
      (node (ref "C38") (pin "1") (pinfunction "1_1") (pintype "passive"))
      (node (ref "C43") (pin "1") (pinfunction "1_1") (pintype "passive"))
      (node (ref "C45") (pin "1") (pinfunction "1_1") (pintype "passive"))
      (node (ref "C61") (pin "1") (pinfunction "1_1") (pintype "passive"))
      (node (ref "R15") (pin "1") (pinfunction "1_1") (pintype "passive"))
      (node (ref "U11") (pin "6") (pinfunction "Vs_6") (pintype "power_in"))
      (node (ref "U13") (pin "6") (pinfunction "Vs_6") (pintype "power_in"))
      (node (ref "U9") (pin "6") (pinfunction "Vs_6") (pintype "power_in"))
    )
    (net (code "42") (name "GND") (class "Default")
      (node (ref "C10") (pin "2") (pinfunction "2_2") (pintype "passive"))
      (node (ref "C32") (pin "1") (pinfunction "1_1") (pintype "passive"))
      (node (ref "C33") (pin "1") (pinfunction "1_1") (pintype "passive"))
      (node (ref "C34") (pin "1") (pinfunction "1_1") (pintype "passive"))
      (node (ref "C35") (pin "2") (pinfunction "2_2") (pintype "passive"))
      (node (ref "C36") (pin "2") (pinfunction "2_2") (pintype "passive"))
      (node (ref "C37") (pin "1") (pinfunction "1_1") (pintype "passive"))
      (node (ref "C38") (pin "2") (pinfunction "2_2") (pintype "passive"))
      (node (ref "C39") (pin "2") (pinfunction "2_2") (pintype "passive"))
      (node (ref "C40") (pin "1") (pinfunction "1_1") (pintype "passive"))
      (node (ref "C41") (pin "1") (pinfunction "1_1") (pintype "passive"))
      (node (ref "C43") (pin "2") (pinfunction "2_2") (pintype "passive"))
      (node (ref "C44") (pin "2") (pinfunction "2_2") (pintype "passive"))
      (node (ref "C45") (pin "2") (pinfunction "2_2") (pintype "passive"))
      (node (ref "C46") (pin "2") (pinfunction "2_2") (pintype "passive"))
      (node (ref "C47") (pin "2") (pinfunction "2_2") (pintype "passive"))
      (node (ref "C48") (pin "2") (pinfunction "2_2") (pintype "passive"))
      (node (ref "C61") (pin "2") (pinfunction "2_2") (pintype "passive"))
      (node (ref "D4") (pin "2") (pinfunction "K_2") (pintype "passive"))
      (node (ref "D5") (pin "2") (pinfunction "K_2") (pintype "passive"))
      (node (ref "D6") (pin "2") (pinfunction "K_2") (pintype "passive"))
      (node (ref "J4") (pin "3") (pinfunction "3_3") (pintype "passive"))
      (node (ref "J4") (pin "5") (pinfunction "5_5") (pintype "passive"))
      (node (ref "J4") (pin "7") (pinfunction "7_7") (pintype "passive"))
      (node (ref "J4") (pin "9") (pinfunction "9_9") (pintype "passive"))
      (node (ref "J5") (pin "15") (pinfunction "15_15") (pintype "passive"))
      (node (ref "J5") (pin "16") (pinfunction "16_16") (pintype "passive"))
      (node (ref "Q4") (pin "2") (pinfunction "E_2") (pintype "passive"))
      (node (ref "R17") (pin "1") (pinfunction "1_1") (pintype "passive"))
      (node (ref "R18") (pin "1") (pinfunction "1_1") (pintype "passive"))
      (node (ref "R43") (pin "2") (pinfunction "2_2") (pintype "passive"))
      (node (ref "R44") (pin "2") (pinfunction "2_2") (pintype "passive"))
      (node (ref "R48") (pin "1") (pinfunction "1_1") (pintype "passive"))
      (node (ref "U11") (pin "2") (pinfunction "GND_2") (pintype "power_in"))
      (node (ref "U11") (pin "3") (pinfunction "REF2_3") (pintype "passive"))
      (node (ref "U11") (pin "4") (pinfunction "NC_4") (pintype "passive"))
      (node (ref "U11") (pin "7") (pinfunction "REF1_7") (pintype "passive"))
      (node (ref "U12") (pin "2") (pinfunction "GND_2") (pintype "power_in"))
      (node (ref "U12") (pin "4") (pinfunction "SOH_4") (pintype "input"))
      (node (ref "U12") (pin "6") (pinfunction "HYSTSET1_6") (pintype "input"))
      (node (ref "U13") (pin "2") (pinfunction "GND_2") (pintype "power_in"))
      (node (ref "U13") (pin "3") (pinfunction "REF2_3") (pintype "passive"))
      (node (ref "U13") (pin "4") (pinfunction "NC_4") (pintype "passive"))
      (node (ref "U13") (pin "7") (pinfunction "REF1_7") (pintype "passive"))
      (node (ref "U8") (pin "49") (pinfunction "Thermal_pad_49") (pintype "passive"))
      (node (ref "U8") (pin "7") (pinfunction "VSS_7") (pintype "power_in"))
      (node (ref "U9") (pin "2") (pinfunction "GND_2") (pintype "power_in"))
      (node (ref "U9") (pin "3") (pinfunction "REF2_3") (pintype "passive"))
      (node (ref "U9") (pin "4") (pinfunction "NC_4") (pintype "passive"))
      (node (ref "U9") (pin "7") (pinfunction "REF1_7") (pintype "passive"))
    )
    (net (code "43") (name "Net-(C41-Pad2)") (class "Default")
      (node (ref "C41") (pin "2") (pinfunction "2_2") (pintype "passive"))
      (node (ref "J5") (pin "12") (pinfunction "12_12") (pintype "passive"))
      (node (ref "R32") (pin "1") (pinfunction "1_1") (pintype "passive"))
    )
    (net (code "44") (name "Net-(D3-K)") (class "Default")
      (node (ref "D3") (pin "2") (pinfunction "K_2") (pintype "passive"))
      (node (ref "R17") (pin "2") (pinfunction "2_2") (pintype "passive"))
    )
    (net (code "45") (name "Net-(D4-A)") (class "Default")
      (node (ref "D4") (pin "1") (pinfunction "A_1") (pintype "passive"))
      (node (ref "R19") (pin "2") (pinfunction "2_2") (pintype "passive"))
    )
    (net (code "46") (name "Net-(D5-A)") (class "Default")
      (node (ref "D5") (pin "1") (pinfunction "A_1") (pintype "passive"))
      (node (ref "R20") (pin "2") (pinfunction "2_2") (pintype "passive"))
    )
    (net (code "47") (name "Net-(D6-A)") (class "Default")
      (node (ref "D6") (pin "1") (pinfunction "A_1") (pintype "passive"))
      (node (ref "R21") (pin "2") (pinfunction "2_2") (pintype "passive"))
    )
    (net (code "48") (name "Net-(J5-Pad11)") (class "Default")
      (node (ref "J5") (pin "11") (pinfunction "11_11") (pintype "passive"))
      (node (ref "R36") (pin "2") (pinfunction "2_2") (pintype "passive"))
    )
    (net (code "49") (name "Net-(J5-Pad13)") (class "Default")
      (node (ref "J5") (pin "13") (pinfunction "13_13") (pintype "passive"))
      (node (ref "R34") (pin "2") (pinfunction "2_2") (pintype "passive"))
    )
    (net (code "50") (name "Net-(Q4-B)") (class "Default")
      (node (ref "Q4") (pin "1") (pinfunction "B_1") (pintype "passive"))
      (node (ref "R38") (pin "1") (pinfunction "1_1") (pintype "passive"))
    )
    (net (code "51") (name "Net-(U8-PA2{slash}ROSC)") (class "Default")
      (node (ref "R18") (pin "2") (pinfunction "2_2") (pintype "passive"))
      (node (ref "U8") (pin "8") (pinfunction "PA2/ROSC_8") (pintype "bidirectional"))
    )
    (net (code "52") (name "Net-(U8-PA15{slash}A1_0)") (class "Default")
      (node (ref "R28") (pin "2") (pinfunction "2_2") (pintype "passive"))
      (node (ref "U8") (pin "30") (pinfunction "PA15/A1_0_30") (pintype "bidirectional"))
    )
    (net (code "53") (name "Net-(U8-PA28)") (class "Default")
      (node (ref "R38") (pin "2") (pinfunction "2_2") (pintype "passive"))
      (node (ref "U8") (pin "3") (pinfunction "PA28_3") (pintype "bidirectional"))
    )
    (net (code "54") (name "Net-(U8-PB2)") (class "Default")
      (node (ref "R33") (pin "2") (pinfunction "2_2") (pintype "passive"))
      (node (ref "U8") (pin "14") (pinfunction "PB2_14") (pintype "bidirectional"))
    )
    (net (code "55") (name "Net-(U8-PB15)") (class "Default")
      (node (ref "R26") (pin "2") (pinfunction "2_2") (pintype "passive"))
      (node (ref "U8") (pin "25") (pinfunction "PB15_25") (pintype "bidirectional"))
    )
    (net (code "56") (name "Net-(U8-PB16)") (class "Default")
      (node (ref "R27") (pin "2") (pinfunction "2_2") (pintype "passive"))
      (node (ref "U8") (pin "26") (pinfunction "PB16_26") (pintype "bidirectional"))
    )
    (net (code "57") (name "Net-(U8-VCORE)") (class "Default")
      (node (ref "C37") (pin "2") (pinfunction "2_2") (pintype "passive"))
      (node (ref "U8") (pin "48") (pinfunction "VCORE_48") (pintype "power_in"))
    )
    (net (code "58") (name "Net-(U9-OUT)") (class "Default")
      (node (ref "R25") (pin "1") (pinfunction "1_1") (pintype "passive"))
      (node (ref "U9") (pin "5") (pinfunction "OUT_5") (pintype "passive"))
    )
    (net (code "59") (name "Net-(U11-OUT)") (class "Default")
      (node (ref "R35") (pin "1") (pinfunction "1_1") (pintype "passive"))
      (node (ref "U11") (pin "5") (pinfunction "OUT_5") (pintype "passive"))
    )
    (net (code "60") (name "Net-(U12-OUT)") (class "Default")
      (node (ref "R39") (pin "1") (pinfunction "1_1") (pintype "passive"))
      (node (ref "U12") (pin "3") (pinfunction "OUT_3") (pintype "output"))
    )
    (net (code "61") (name "Net-(U13-OUT)") (class "Default")
      (node (ref "R40") (pin "1") (pinfunction "1_1") (pintype "passive"))
      (node (ref "U13") (pin "5") (pinfunction "OUT_5") (pintype "passive"))
    )
    (net (code "62") (name "VCC_3V3") (class "Default")
      (node (ref "C32") (pin "2") (pinfunction "2_2") (pintype "passive"))
      (node (ref "C33") (pin "2") (pinfunction "2_2") (pintype "passive"))
      (node (ref "C46") (pin "1") (pinfunction "1_1") (pintype "passive"))
      (node (ref "D3") (pin "1") (pinfunction "A_1") (pintype "passive"))
      (node (ref "J4") (pin "1") (pinfunction "1_1") (pintype "passive"))
      (node (ref "R15") (pin "2") (pinfunction "2_2") (pintype "passive"))
      (node (ref "R16") (pin "1") (pinfunction "1_1") (pintype "passive"))
      (node (ref "R32") (pin "2") (pinfunction "2_2") (pintype "passive"))
      (node (ref "R37") (pin "1") (pinfunction "1_1") (pintype "passive"))
      (node (ref "R41") (pin "1") (pinfunction "1_1") (pintype "passive"))
      (node (ref "R42") (pin "1") (pinfunction "1_1") (pintype "passive"))
      (node (ref "U12") (pin "1") (pinfunction "HYSTSET0_1") (pintype "input"))
      (node (ref "U12") (pin "5") (pinfunction "VS_5") (pintype "power_in"))
      (node (ref "U8") (pin "6") (pinfunction "VDD_6") (pintype "power_in"))
    )
    (net (code "63") (name "unconnected-(J4-Pad6)") (class "Default")
      (node (ref "J4") (pin "6") (pinfunction "6_6") (pintype "passive"))
    )
    (net (code "64") (name "unconnected-(J4-Pad8)") (class "Default")
      (node (ref "J4") (pin "8") (pinfunction "8_8") (pintype "passive"))
    )
    (net (code "65") (name "unconnected-(U8-PA3{slash}LFXIN-Pad9)") (class "Default")
      (node (ref "U8") (pin "9") (pinfunction "PA3/LFXIN_9") (pintype "bidirectional"))
    )
    (net (code "66") (name "unconnected-(U8-PA9-Pad17)") (class "Default")
      (node (ref "U8") (pin "17") (pinfunction "PA9_17") (pintype "bidirectional"))
    )
    (net (code "67") (name "unconnected-(U8-PA10-Pad18)") (class "Default")
      (node (ref "U8") (pin "18") (pinfunction "PA10_18") (pintype "bidirectional"))
    )
    (net (code "68") (name "unconnected-(U8-PA11-Pad19)") (class "Default")
      (node (ref "U8") (pin "19") (pinfunction "PA11_19") (pintype "bidirectional"))
    )
    (net (code "69") (name "unconnected-(U8-PA21{slash}A1_7{slash}VREF--Pad39)") (class "Default")
      (node (ref "U8") (pin "39") (pinfunction "PA21/A1_7/VREF-_39") (pintype "bidirectional"))
    )
    (net (code "70") (name "unconnected-(U8-PB8-Pad22)") (class "Default")
      (node (ref "U8") (pin "22") (pinfunction "PB8_22") (pintype "bidirectional"))
    )
    (net (code "71") (name "unconnected-(U8-PB9-Pad23)") (class "Default")
      (node (ref "U8") (pin "23") (pinfunction "PB9_23") (pintype "bidirectional"))
    )
    (net (code "72") (name "unconnected-(U8-PB14-Pad24)") (class "Default")
      (node (ref "U8") (pin "24") (pinfunction "PB14_24") (pintype "bidirectional"))
    )
    (net (code "73") (name "unconnected-(U8-PB20{slash}A0_6-Pad41)") (class "Default")
      (node (ref "U8") (pin "41") (pinfunction "PB20/A0_6_41") (pintype "bidirectional"))
    )
    (net (code "74") (name "unconnected-(U8-PB24{slash}A0_5-Pad42)") (class "Default")
      (node (ref "U8") (pin "42") (pinfunction "PB24/A0_5_42") (pintype "bidirectional"))
    )
  )
)
